# 02_MCU.net
KiCad netlist of a schematic drawn in Altium Designer
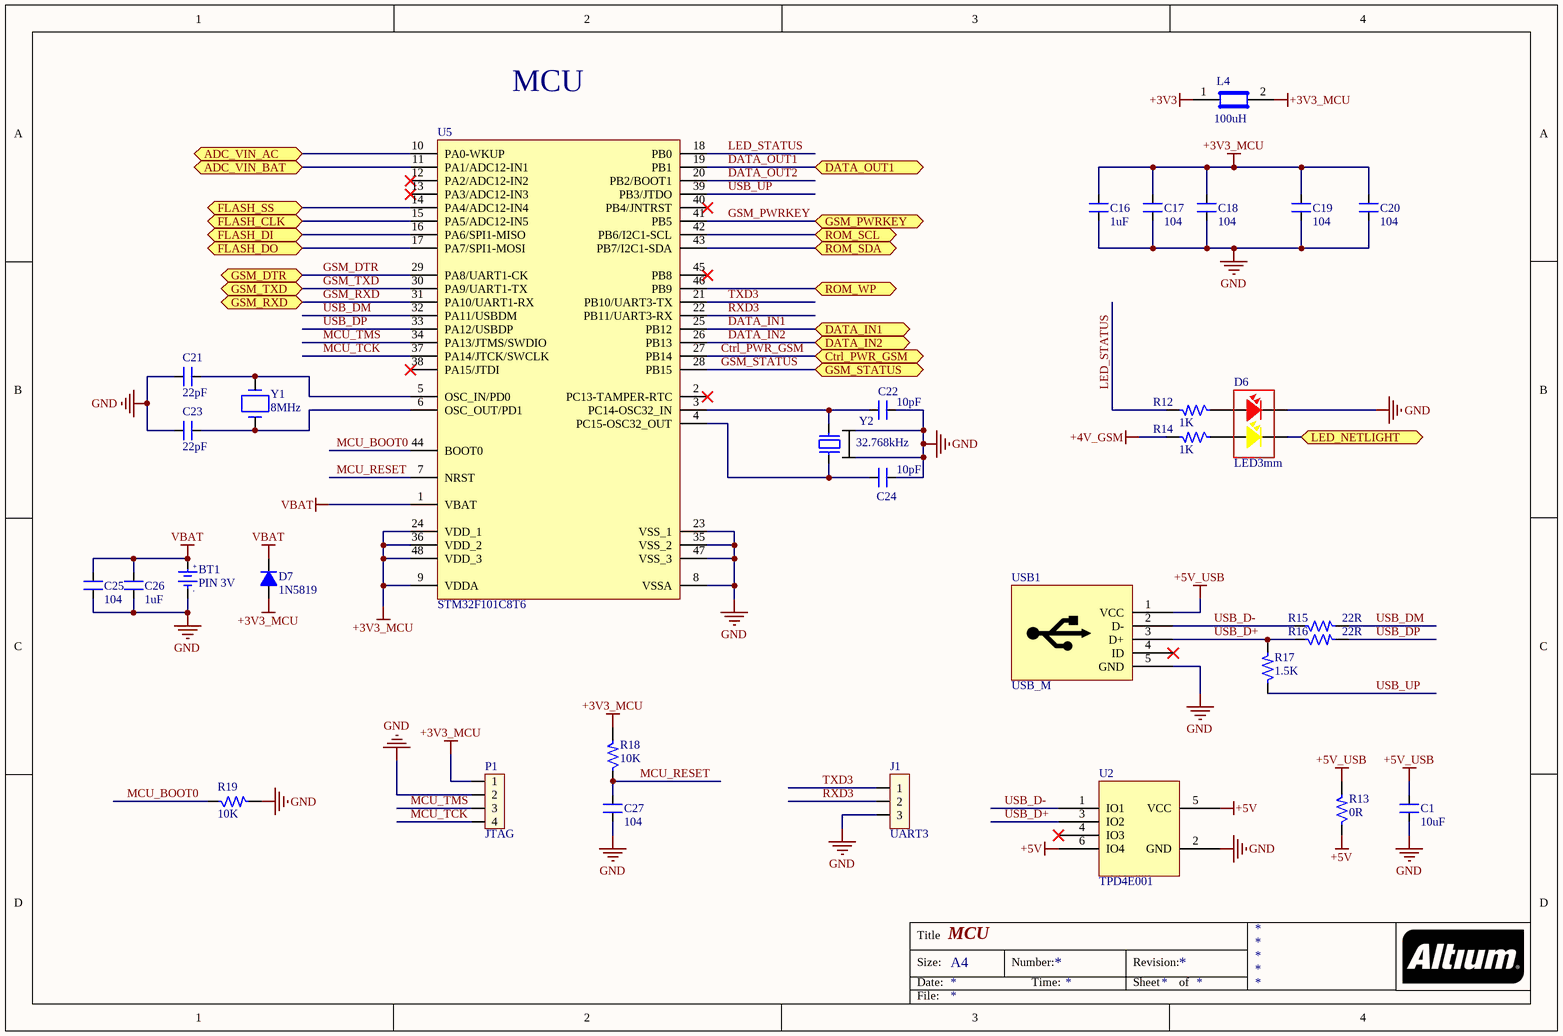
[diagram p0: [02] MCU.SchDoc]

(export (version "E")
  (design (tool "Eeschema 10.0.6"))
  (components
    (comp (ref "BT1")
      (value "PIN 3V")
      (footprint "CR1220 socket")
      (description "Battery 3VDC")
      (libsource (lib "khapham") (part "PIN 3V"))
    )
    (comp (ref "C1")
      (value "10uF")
      (footprint "C0603 SMT")
      (description "Cap SMD")
      (libsource (lib "khapham") (part "CM"))
    )
    (comp (ref "C16")
      (value "1uF")
      (footprint "C0603 SMT")
      (description "Cap SMD")
      (libsource (lib "khapham") (part "CM"))
    )
    (comp (ref "C17")
      (value "104")
      (footprint "C0603 SMT")
      (description "Cap SMD")
      (libsource (lib "khapham") (part "CM"))
    )
    (comp (ref "C18")
      (value "104")
      (footprint "C0603 SMT")
      (description "Cap SMD")
      (libsource (lib "khapham") (part "CM"))
    )
    (comp (ref "C19")
      (value "104")
      (footprint "C0603 SMT")
      (description "Cap SMD")
      (libsource (lib "khapham") (part "CM"))
    )
    (comp (ref "C20")
      (value "104")
      (footprint "C0603 SMT")
      (description "Cap SMD")
      (libsource (lib "khapham") (part "CM"))
    )
    (comp (ref "C21")
      (value "22pF")
      (footprint "C0603 SMT")
      (description "Cap SMD")
      (libsource (lib "khapham") (part "CM"))
    )
    (comp (ref "C22")
      (value "10pF")
      (footprint "C0603 SMT")
      (description "Cap SMD")
      (libsource (lib "khapham") (part "CM"))
    )
    (comp (ref "C23")
      (value "22pF")
      (footprint "C0603 SMT")
      (description "Cap SMD")
      (libsource (lib "khapham") (part "CM"))
    )
    (comp (ref "C24")
      (value "10pF")
      (footprint "C0603 SMT")
      (description "Cap SMD")
      (libsource (lib "khapham") (part "CM"))
    )
    (comp (ref "C25")
      (value "104")
      (footprint "C0603 SMT")
      (description "Cap SMD")
      (libsource (lib "khapham") (part "CM"))
    )
    (comp (ref "C26")
      (value "1uF")
      (footprint "C0603 SMT")
      (description "Cap SMD")
      (libsource (lib "khapham") (part "CM"))
    )
    (comp (ref "C27")
      (value "104")
      (footprint "C0603 SMT")
      (description "Cap SMD")
      (libsource (lib "khapham") (part "CM"))
    )
    (comp (ref "D6")
      (value "LED3mm")
      (footprint "LED 2 holder 3mm")
      (description "LED 2 holder RGB 3mm")
      (libsource (lib "khapham") (part "LED2Holder_3"))
    )
    (comp (ref "D7")
      (value "1N5819")
      (footprint "SOD123")
      (description "Diode 1A")
      (libsource (lib "khapham") (part "D1A"))
    )
    (comp (ref "J1")
      (value "UART3")
      (footprint "JP3")
      (description "Jumper 3")
      (libsource (lib "khapham") (part "JP3"))
    )
    (comp (ref "L4")
      (value "100uH")
      (footprint "R0805")
      (description "100uH 0805")
      (libsource (lib "khapham") (part "Ferrite Bead"))
    )
    (comp (ref "P1") (value "JTAG") (footprint "JP1x4") (libsource (lib "khapham") (part "JP4")))
    (comp (ref "R12")
      (value "1K")
      (footprint "R0603 -SMT")
      (description "Resistor SMD")
      (libsource (lib "khapham") (part "RM"))
    )
    (comp (ref "R13")
      (value "0R")
      (footprint "R0805 SMT")
      (description "Resistor SMD")
      (libsource (lib "khapham") (part "RM"))
    )
    (comp (ref "R14")
      (value "1K")
      (footprint "R0603 -SMT")
      (description "Resistor SMD")
      (libsource (lib "khapham") (part "RM"))
    )
    (comp (ref "R15")
      (value "22R")
      (footprint "R0603 -SMT")
      (description "Resistor SMD")
      (libsource (lib "khapham") (part "RM"))
    )
    (comp (ref "R16")
      (value "22R")
      (footprint "R0603 -SMT")
      (description "Resistor SMD")
      (libsource (lib "khapham") (part "RM"))
    )
    (comp (ref "R17")
      (value "1.5K")
      (footprint "R0603 -SMT")
      (description "Resistor SMD")
      (libsource (lib "khapham") (part "RM"))
    )
    (comp (ref "R18")
      (value "10K")
      (footprint "R0603 -SMT")
      (description "Resistor SMD")
      (libsource (lib "khapham") (part "RM"))
    )
    (comp (ref "R19")
      (value "10K")
      (footprint "R0603 -SMT")
      (description "Resistor SMD")
      (libsource (lib "khapham") (part "RM"))
    )
    (comp (ref "U2")
      (value "TPD4E001")
      (footprint "TPD4E001 DBV")
      (libsource (lib "khapham") (part "TPD4E001"))
    )
    (comp (ref "U5")
      (value "STM32F101C8T6")
      (footprint "LQFP48-B")
      (description "STM32 ARM-based 32-bit MCU with 32 Kbytes Flash, 48-pin LQFP, Industrial Temperature")
      (libsource (lib "khapham") (part "STM32F101C8T6"))
    )
    (comp (ref "USB1")
      (value "USB_M")
      (footprint "USB_B_MINI_SMD")
      (libsource (lib "khapham") (part "USB_M"))
    )
    (comp (ref "Y1")
      (value "8MHz")
      (footprint "ABM7_v1_1_BIG")
      (description "CRYSTAL 16MHZ 18PF SMD")
      (fields
        (field (name "MANUFACTURER") "Abracon LLC")
        (field (name "MANUFACTURER PART NUMBER") "ABM7-16.000MHZ-D2Y-T")
        (field (name ".CREATOR") "MM")
        (field (name ".CHECKED PCB") "RF")
        (field (name ".CHECKED SCH") "RF")
      )
      (libsource (lib "LED_Display ") (part "ABM7-16.000MHZ-D2Y-T"))
    )
    (comp (ref "Y2")
      (value "32.768kHz")
      (footprint "XT-SMD MC306")
      (description "Crystal SMD 6035 - 4 Pads")
      (libsource (lib "khapham") (part "XT4_SMD_MC306"))
    )
  )
  (nets
    (net (code "1") (name "+3V3") (class "Default")
      (node (ref "L4") (pin "1") (pinfunction "1_1") (pintype "passive"))
    )
    (net (code "2") (name "+3V3_MCU") (class "Default")
      (node (ref "C16") (pin "2") (pinfunction "2_2") (pintype "passive"))
      (node (ref "C17") (pin "2") (pinfunction "2_2") (pintype "passive"))
      (node (ref "C18") (pin "2") (pinfunction "2_2") (pintype "passive"))
      (node (ref "C19") (pin "2") (pinfunction "2_2") (pintype "passive"))
      (node (ref "C20") (pin "2") (pinfunction "2_2") (pintype "passive"))
      (node (ref "D7") (pin "1") (pinfunction "A_1") (pintype "passive"))
      (node (ref "L4") (pin "2") (pinfunction "2_2") (pintype "passive"))
      (node (ref "P1") (pin "1") (pinfunction "1_1") (pintype "passive"))
      (node (ref "R18") (pin "2") (pinfunction "2_2") (pintype "passive"))
      (node (ref "U5") (pin "24") (pinfunction "VDD_1_24") (pintype "passive"))
      (node (ref "U5") (pin "36") (pinfunction "VDD_2_36") (pintype "passive"))
      (node (ref "U5") (pin "48") (pinfunction "VDD_3_48") (pintype "passive"))
      (node (ref "U5") (pin "9") (pinfunction "VDDA_9") (pintype "passive"))
    )
    (net (code "3") (name "+4V_GSM") (class "Default")
      (node (ref "R14") (pin "2") (pinfunction "2_2") (pintype "passive"))
    )
    (net (code "4") (name "+5V") (class "Default")
      (node (ref "R13") (pin "1") (pinfunction "1_1") (pintype "passive"))
      (node (ref "U2") (pin "5") (pinfunction "VCC_5") (pintype "passive"))
      (node (ref "U2") (pin "6") (pinfunction "IO4_6") (pintype "passive"))
    )
    (net (code "5") (name "+5V_USB") (class "Default")
      (node (ref "C1") (pin "2") (pinfunction "2_2") (pintype "passive"))
      (node (ref "R13") (pin "2") (pinfunction "2_2") (pintype "passive"))
      (node (ref "USB1") (pin "1") (pinfunction "VCC_1") (pintype "passive"))
    )
    (net (code "6") (name "/ADC_VIN_AC") (class "Default")
      (node (ref "U5") (pin "10") (pinfunction "PA0-WKUP_10") (pintype "passive"))
    )
    (net (code "7") (name "/ADC_VIN_BAT") (class "Default")
      (node (ref "U5") (pin "11") (pinfunction "PA1/ADC12-IN1_11") (pintype "passive"))
    )
    (net (code "8") (name "/Ctrl_PWR_GSM") (class "Default")
      (node (ref "U5") (pin "27") (pinfunction "PB14_27") (pintype "passive"))
    )
    (net (code "9") (name "/DATA_IN1") (class "Default")
      (node (ref "U5") (pin "25") (pinfunction "PB12_25") (pintype "passive"))
    )
    (net (code "10") (name "/DATA_IN2") (class "Default")
      (node (ref "U5") (pin "26") (pinfunction "PB13_26") (pintype "passive"))
    )
    (net (code "11") (name "/DATA_OUT1") (class "Default")
      (node (ref "U5") (pin "19") (pinfunction "PB1_19") (pintype "passive"))
    )
    (net (code "12") (name "/DATA_OUT2") (class "Default")
      (node (ref "U5") (pin "20") (pinfunction "PB2/BOOT1_20") (pintype "passive"))
    )
    (net (code "13") (name "/FLASH_CLK") (class "Default")
      (node (ref "U5") (pin "15") (pinfunction "PA5/ADC12-IN5_15") (pintype "passive"))
    )
    (net (code "14") (name "/FLASH_DI") (class "Default")
      (node (ref "U5") (pin "16") (pinfunction "PA6/SPI1-MISO_16") (pintype "passive"))
    )
    (net (code "15") (name "/FLASH_DO") (class "Default")
      (node (ref "U5") (pin "17") (pinfunction "PA7/SPI1-MOSI_17") (pintype "passive"))
    )
    (net (code "16") (name "/FLASH_SS") (class "Default")
      (node (ref "U5") (pin "14") (pinfunction "PA4/ADC12-IN4_14") (pintype "passive"))
    )
    (net (code "17") (name "/GSM_DTR") (class "Default")
      (node (ref "U5") (pin "29") (pinfunction "PA8/UART1-CK_29") (pintype "passive"))
    )
    (net (code "18") (name "/GSM_PWRKEY") (class "Default")
      (node (ref "U5") (pin "41") (pinfunction "PB5_41") (pintype "passive"))
    )
    (net (code "19") (name "/GSM_RXD") (class "Default")
      (node (ref "U5") (pin "31") (pinfunction "PA10/UART1-RX_31") (pintype "passive"))
    )
    (net (code "20") (name "/GSM_STATUS") (class "Default")
      (node (ref "U5") (pin "28") (pinfunction "PB15_28") (pintype "passive"))
    )
    (net (code "21") (name "/GSM_TXD") (class "Default")
      (node (ref "U5") (pin "30") (pinfunction "PA9/UART1-TX_30") (pintype "passive"))
    )
    (net (code "22") (name "/LED_NETLIGHT") (class "Default")
      (node (ref "D6") (pin "3") (pinfunction "3_3") (pintype "passive"))
    )
    (net (code "23") (name "/LED_STATUS") (class "Default")
      (node (ref "R12") (pin "2") (pinfunction "2_2") (pintype "passive"))
      (node (ref "U5") (pin "18") (pinfunction "PB0_18") (pintype "passive"))
    )
    (net (code "24") (name "/MCU_BOOT0") (class "Default")
      (node (ref "R19") (pin "1") (pinfunction "1_1") (pintype "passive"))
      (node (ref "U5") (pin "44") (pinfunction "BOOT0_44") (pintype "passive"))
    )
    (net (code "25") (name "/MCU_RESET") (class "Default")
      (node (ref "C27") (pin "1") (pinfunction "1_1") (pintype "passive"))
      (node (ref "R18") (pin "1") (pinfunction "1_1") (pintype "passive"))
      (node (ref "U5") (pin "7") (pinfunction "NRST_7") (pintype "passive"))
    )
    (net (code "26") (name "/MCU_TCK") (class "Default")
      (node (ref "P1") (pin "4") (pinfunction "4_4") (pintype "passive"))
      (node (ref "U5") (pin "37") (pinfunction "PA14/JTCK/SWCLK_37") (pintype "passive"))
    )
    (net (code "27") (name "/MCU_TMS") (class "Default")
      (node (ref "P1") (pin "3") (pinfunction "3_3") (pintype "passive"))
      (node (ref "U5") (pin "34") (pinfunction "PA13/JTMS/SWDIO_34") (pintype "passive"))
    )
    (net (code "28") (name "/ROM_SCL") (class "Default")
      (node (ref "U5") (pin "42") (pinfunction "PB6/I2C1-SCL_42") (pintype "passive"))
    )
    (net (code "29") (name "/ROM_SDA") (class "Default")
      (node (ref "U5") (pin "43") (pinfunction "PB7/I2C1-SDA_43") (pintype "passive"))
    )
    (net (code "30") (name "/ROM_WP") (class "Default")
      (node (ref "U5") (pin "46") (pinfunction "PB9_46") (pintype "passive"))
    )
    (net (code "31") (name "/RXD3") (class "Default")
      (node (ref "J1") (pin "2") (pinfunction "2_2") (pintype "passive"))
      (node (ref "U5") (pin "22") (pinfunction "PB11/UART3-RX_22") (pintype "passive"))
    )
    (net (code "32") (name "/TXD3") (class "Default")
      (node (ref "J1") (pin "1") (pinfunction "1_1") (pintype "passive"))
      (node (ref "U5") (pin "21") (pinfunction "PB10/UART3-TX_21") (pintype "passive"))
    )
    (net (code "33") (name "/USB_D+") (class "Default")
      (node (ref "R16") (pin "1") (pinfunction "1_1") (pintype "passive"))
      (node (ref "R17") (pin "2") (pinfunction "2_2") (pintype "passive"))
      (node (ref "U2") (pin "3") (pinfunction "IO2_3") (pintype "passive"))
      (node (ref "USB1") (pin "3") (pinfunction "D+_3") (pintype "passive"))
    )
    (net (code "34") (name "/USB_D-") (class "Default")
      (node (ref "R15") (pin "1") (pinfunction "1_1") (pintype "passive"))
      (node (ref "U2") (pin "1") (pinfunction "IO1_1") (pintype "passive"))
      (node (ref "USB1") (pin "2") (pinfunction "D-_2") (pintype "passive"))
    )
    (net (code "35") (name "/USB_DM") (class "Default")
      (node (ref "R15") (pin "2") (pinfunction "2_2") (pintype "passive"))
      (node (ref "U5") (pin "32") (pinfunction "PA11/USBDM_32") (pintype "passive"))
    )
    (net (code "36") (name "/USB_DP") (class "Default")
      (node (ref "R16") (pin "2") (pinfunction "2_2") (pintype "passive"))
      (node (ref "U5") (pin "33") (pinfunction "PA12/USBDP_33") (pintype "passive"))
    )
    (net (code "37") (name "/USB_UP") (class "Default")
      (node (ref "R17") (pin "1") (pinfunction "1_1") (pintype "passive"))
      (node (ref "U5") (pin "39") (pinfunction "PB3/JTDO_39") (pintype "passive"))
    )
    (net (code "38") (name "GND") (class "Default")
      (node (ref "BT1") (pin "2") (pinfunction "GND_2") (pintype "passive"))
      (node (ref "C1") (pin "1") (pinfunction "1_1") (pintype "passive"))
      (node (ref "C16") (pin "1") (pinfunction "1_1") (pintype "passive"))
      (node (ref "C17") (pin "1") (pinfunction "1_1") (pintype "passive"))
      (node (ref "C18") (pin "1") (pinfunction "1_1") (pintype "passive"))
      (node (ref "C19") (pin "1") (pinfunction "1_1") (pintype "passive"))
      (node (ref "C20") (pin "1") (pinfunction "1_1") (pintype "passive"))
      (node (ref "C21") (pin "2") (pinfunction "2_2") (pintype "passive"))
      (node (ref "C22") (pin "2") (pinfunction "2_2") (pintype "passive"))
      (node (ref "C23") (pin "2") (pinfunction "2_2") (pintype "passive"))
      (node (ref "C24") (pin "2") (pinfunction "2_2") (pintype "passive"))
      (node (ref "C25") (pin "1") (pinfunction "1_1") (pintype "passive"))
      (node (ref "C26") (pin "1") (pinfunction "1_1") (pintype "passive"))
      (node (ref "C27") (pin "2") (pinfunction "2_2") (pintype "passive"))
      (node (ref "D6") (pin "1") (pinfunction "1_1") (pintype "passive"))
      (node (ref "J1") (pin "3") (pinfunction "3_3") (pintype "passive"))
      (node (ref "P1") (pin "2") (pinfunction "2_2") (pintype "passive"))
      (node (ref "R19") (pin "2") (pinfunction "2_2") (pintype "passive"))
      (node (ref "U2") (pin "2") (pinfunction "GND_2") (pintype "passive"))
      (node (ref "U5") (pin "23") (pinfunction "VSS_1_23") (pintype "passive"))
      (node (ref "U5") (pin "35") (pinfunction "VSS_2_35") (pintype "passive"))
      (node (ref "U5") (pin "47") (pinfunction "VSS_3_47") (pintype "passive"))
      (node (ref "U5") (pin "8") (pinfunction "VSSA_8") (pintype "passive"))
      (node (ref "USB1") (pin "5") (pinfunction "GND_5") (pintype "passive"))
      (node (ref "Y2") (pin "2") (pinfunction "2_2") (pintype "passive"))
      (node (ref "Y2") (pin "3") (pinfunction "3_3") (pintype "passive"))
    )
    (net (code "39") (name "Net-(D6-Pad2)") (class "Default")
      (node (ref "D6") (pin "2") (pinfunction "2_2") (pintype "passive"))
      (node (ref "R12") (pin "1") (pinfunction "1_1") (pintype "passive"))
    )
    (net (code "40") (name "Net-(D6-Pad4)") (class "Default")
      (node (ref "D6") (pin "4") (pinfunction "4_4") (pintype "passive"))
      (node (ref "R14") (pin "1") (pinfunction "1_1") (pintype "passive"))
    )
    (net (code "41") (name "Net-(U5-OSC_IN{slash}PD0)") (class "Default")
      (node (ref "C21") (pin "1") (pinfunction "1_1") (pintype "passive"))
      (node (ref "U5") (pin "5") (pinfunction "OSC_IN/PD0_5") (pintype "passive"))
      (node (ref "Y1") (pin "1") (pinfunction "1_1") (pintype "passive"))
    )
    (net (code "42") (name "Net-(U5-OSC_OUT{slash}PD1)") (class "Default")
      (node (ref "C23") (pin "1") (pinfunction "1_1") (pintype "passive"))
      (node (ref "U5") (pin "6") (pinfunction "OSC_OUT/PD1_6") (pintype "passive"))
      (node (ref "Y1") (pin "2") (pinfunction "2_2") (pintype "passive"))
    )
    (net (code "43") (name "Net-(U5-PC14-OSC32_IN)") (class "Default")
      (node (ref "C22") (pin "1") (pinfunction "1_1") (pintype "passive"))
      (node (ref "U5") (pin "3") (pinfunction "PC14-OSC32_IN_3") (pintype "passive"))
      (node (ref "Y2") (pin "1") (pinfunction "1_1") (pintype "passive"))
    )
    (net (code "44") (name "Net-(U5-PC15-OSC32_OUT)") (class "Default")
      (node (ref "C24") (pin "1") (pinfunction "1_1") (pintype "passive"))
      (node (ref "U5") (pin "4") (pinfunction "PC15-OSC32_OUT_4") (pintype "passive"))
      (node (ref "Y2") (pin "4") (pinfunction "4_4") (pintype "passive"))
    )
    (net (code "45") (name "VBAT") (class "Default")
      (node (ref "BT1") (pin "1") (pinfunction "+3V_1") (pintype "passive"))
      (node (ref "C25") (pin "2") (pinfunction "2_2") (pintype "passive"))
      (node (ref "C26") (pin "2") (pinfunction "2_2") (pintype "passive"))
      (node (ref "D7") (pin "2") (pinfunction "K_2") (pintype "passive"))
      (node (ref "U5") (pin "1") (pinfunction "VBAT_1") (pintype "passive"))
    )
    (net (code "46") (name "unconnected-(U2-IO3-Pad4)") (class "Default")
      (node (ref "U2") (pin "4") (pinfunction "IO3_4") (pintype "passive+no_connect"))
    )
    (net (code "47") (name "unconnected-(U5-PA2{slash}ADC12-IN2-Pad12)") (class "Default")
      (node (ref "U5") (pin "12") (pinfunction "PA2/ADC12-IN2_12") (pintype "passive+no_connect"))
    )
    (net (code "48") (name "unconnected-(U5-PA3{slash}ADC12-IN3-Pad13)") (class "Default")
      (node (ref "U5") (pin "13") (pinfunction "PA3/ADC12-IN3_13") (pintype "passive+no_connect"))
    )
    (net (code "49") (name "unconnected-(U5-PA15{slash}JTDI-Pad38)") (class "Default")
      (node (ref "U5") (pin "38") (pinfunction "PA15/JTDI_38") (pintype "passive+no_connect"))
    )
    (net (code "50") (name "unconnected-(U5-PB4{slash}JNTRST-Pad40)") (class "Default")
      (node (ref "U5") (pin "40") (pinfunction "PB4/JNTRST_40") (pintype "passive+no_connect"))
    )
    (net (code "51") (name "unconnected-(U5-PB8-Pad45)") (class "Default")
      (node (ref "U5") (pin "45") (pinfunction "PB8_45") (pintype "passive+no_connect"))
    )
    (net (code "52") (name "unconnected-(U5-PC13-TAMPER-RTC-Pad2)") (class "Default")
      (node (ref "U5") (pin "2") (pinfunction "PC13-TAMPER-RTC_2") (pintype "passive+no_connect"))
    )
    (net (code "53") (name "unconnected-(USB1-ID-Pad4)") (class "Default")
      (node (ref "USB1") (pin "4") (pinfunction "ID_4") (pintype "passive+no_connect"))
    )
  )
)
